# BMW_Side_Turn_Signal.net
KiCad netlist of a schematic drawn in Altium Designer
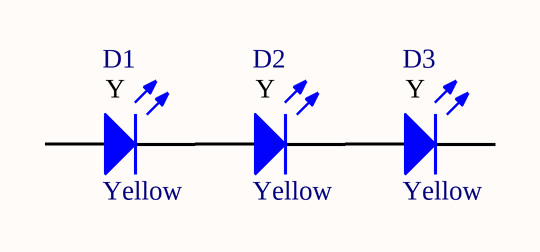
[diagram p0: BMW Side Turn Signal.SchDoc]

(export (version "E")
  (design (tool "Eeschema 10.0.6"))
  (components
    (comp (ref "D1")
      (value "Yellow")
      (footprint "LED:LED Round 5mm Yellow")
      (description "2.8-3v 25mA, 4-5cd")
      (libsource (lib "LED") (part "Led Round 5mm Yellow"))
    )
    (comp (ref "D2")
      (value "Yellow")
      (footprint "LED:LED Round 5mm Yellow")
      (description "2.8-3v 25mA, 4-5cd")
      (libsource (lib "LED") (part "Led Round 5mm Yellow"))
    )
    (comp (ref "D3")
      (value "Yellow")
      (footprint "LED:LED Round 5mm Yellow")
      (description "2.8-3v 25mA, 4-5cd")
      (libsource (lib "LED") (part "Led Round 5mm Yellow"))
    )
  )
  (nets
    (net (code "1") (name "Net-(D1-K)") (class "Default")
      (node (ref "D1") (pin "2") (pinfunction "K_2") (pintype "passive"))
      (node (ref "D2") (pin "1") (pinfunction "A_1") (pintype "passive"))
    )
    (net (code "2") (name "Net-(D2-K)") (class "Default")
      (node (ref "D2") (pin "2") (pinfunction "K_2") (pintype "passive"))
      (node (ref "D3") (pin "1") (pinfunction "A_1") (pintype "passive"))
    )
    (net (code "3") (name "unconnected-(D1-A-Pad1)") (class "Default")
      (node (ref "D1") (pin "1") (pinfunction "A_1") (pintype "passive"))
    )
    (net (code "4") (name "unconnected-(D3-K-Pad2)") (class "Default")
      (node (ref "D3") (pin "2") (pinfunction "K_2") (pintype "passive"))
    )
  )
)
